# RS232.net
KiCad netlist of a schematic drawn in Altium Designer
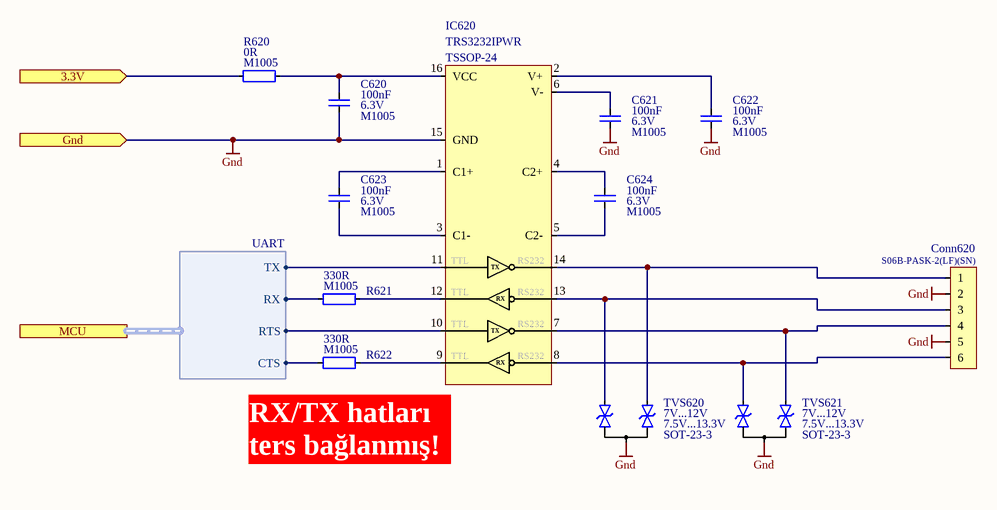
[diagram p0: RS232.SchDoc]

(export (version "E")
  (design (tool "Eeschema 10.0.6"))
  (components
    (comp (ref "C620")
      (value "100nF")
      (footprint "Capacitor_Ceramic_M1005_I0402")
      (description "Cap, Cer, 100nF, 6.3V, M1005")
      (fields
        (field (name "VOLTAGE") "6.3V")
        (field (name "MANUFACTURER PART NUMBER") "04026D104KAT4A")
        (field (name "MANUFACTURER") "Kyocera")
        (field (name "PACKAGE") "M1005")
      )
      (libsource (lib "Capacitor") (part "Capacitor_Ceramic"))
    )
    (comp (ref "C621")
      (value "100nF")
      (footprint "Capacitor_Ceramic_M1005_I0402")
      (description "Cap, Cer, 100nF, 6.3V, M1005")
      (fields
        (field (name "VOLTAGE") "6.3V")
        (field (name "MANUFACTURER PART NUMBER") "04026D104KAT4A")
        (field (name "MANUFACTURER") "Kyocera")
        (field (name "PACKAGE") "M1005")
      )
      (libsource (lib "Capacitor") (part "Capacitor_Ceramic"))
    )
    (comp (ref "C622")
      (value "100nF")
      (footprint "Capacitor_Ceramic_M1005_I0402")
      (description "Cap, Cer, 100nF, 6.3V, M1005")
      (fields
        (field (name "VOLTAGE") "6.3V")
        (field (name "MANUFACTURER PART NUMBER") "04026D104KAT4A")
        (field (name "MANUFACTURER") "Kyocera")
        (field (name "PACKAGE") "M1005")
      )
      (libsource (lib "Capacitor") (part "Capacitor_Ceramic"))
    )
    (comp (ref "C623")
      (value "100nF")
      (footprint "Capacitor_Ceramic_M1005_I0402")
      (description "Cap, Cer, 100nF, 6.3V, M1005")
      (fields
        (field (name "VOLTAGE") "6.3V")
        (field (name "MANUFACTURER PART NUMBER") "04026D104KAT4A")
        (field (name "MANUFACTURER") "Kyocera")
        (field (name "PACKAGE") "M1005")
      )
      (libsource (lib "Capacitor") (part "Capacitor_Ceramic"))
    )
    (comp (ref "C624")
      (value "100nF")
      (footprint "Capacitor_Ceramic_M1005_I0402")
      (description "Cap, Cer, 100nF, 6.3V, M1005")
      (fields
        (field (name "VOLTAGE") "6.3V")
        (field (name "MANUFACTURER PART NUMBER") "04026D104KAT4A")
        (field (name "MANUFACTURER") "Kyocera")
        (field (name "PACKAGE") "M1005")
      )
      (libsource (lib "Capacitor") (part "Capacitor_Ceramic"))
    )
    (comp (ref "Conn620")
      (value "Connector - 6P")
      (footprint "Connector, S06B-PASK-2")
      (description "Conn, JST, 6P, TH, PA, Side Entry")
      (fields
        (field (name "MANUFACTURER") "JST")
        (field (name "MANUFACTURER PART NUMBER") "S06B-PASK-2(LF)(SN)")
      )
      (libsource (lib "Connector - JST") (part "Connector - 6P"))
    )
    (comp (ref "IC620")
      (value "RS232 - Texas, TRS3232IPWR")
      (footprint "TSSOP-16")
      (description "IC, Interface, RS232, TSSOP-24")
      (fields
        (field (name "MANUFACTURER") "Texas")
        (field (name "MANUFACTURER PART NUMBER") "TRS3232IPWR")
        (field (name "PACKAGE") "TSSOP-24")
      )
      (libsource (lib "IC - Interface") (part "RS232 - Texas, TRS3232IPWR"))
    )
    (comp (ref "R620")
      (value "0R")
      (footprint "Resistor_Smd_M1005_I0402")
      (description "Res, 0R, M1005")
      (fields
        (field (name "MANUFACTURER") "Yageo")
        (field (name "MANUFACTURER PART NUMBER") "RC0402FR-070RL")
        (field (name "PACKAGE") "M1005")
      )
      (libsource (lib "Resistor") (part "Resistor"))
    )
    (comp (ref "R621")
      (value "330R")
      (footprint "Resistor_Smd_M1005_I0402")
      (description "Res, 330R, 1%, M1005")
      (fields
        (field (name "TOLERANCE") "1%")
        (field (name "MANUFACTURER") "Yageo")
        (field (name "PACKAGE") "M1005")
      )
      (libsource (lib "Resistor") (part "Resistor"))
    )
    (comp (ref "R622")
      (value "330R")
      (footprint "Resistor_Smd_M1005_I0402")
      (description "Res, 330R, 1%, M1005")
      (fields
        (field (name "TOLERANCE") "1%")
        (field (name "MANUFACTURER") "Yageo")
        (field (name "PACKAGE") "M1005")
      )
      (libsource (lib "Resistor") (part "Resistor"))
    )
    (comp (ref "TVS620")
      (value "Diode_Tvs_2P_Bidirectional")
      (footprint "Diode_SOT-23-3_2P_Bidirectional_Type_1")
      (description "TVS, 2P, Bidirectional, 7V/12V, SOT-23-3")
      (fields
        (field (name "MANUFACTURER PART NUMBER") "CDSOT23-SM712")
        (field (name "MANUFACTURER") "Bourns")
        (field (name "VOLTAGE, BREAK DOWN") "7.5V...13.3V")
        (field (name "VOLTAGE, STAND OFF") "7V...12V")
        (field (name "PACKAGE") "SOT-23-3")
      )
      (libsource (lib "Diode") (part "Diode_Tvs_2P_Bidirectional"))
    )
    (comp (ref "TVS621")
      (value "Diode_Tvs_2P_Bidirectional")
      (footprint "Diode_SOT-23-3_2P_Bidirectional_Type_1")
      (description "TVS, 2P, Bidirectional, 7V/12V, SOT-23-3")
      (fields
        (field (name "MANUFACTURER PART NUMBER") "CDSOT23-SM712")
        (field (name "MANUFACTURER") "Bourns")
        (field (name "VOLTAGE, BREAK DOWN") "7.5V...13.3V")
        (field (name "VOLTAGE, STAND OFF") "7V...12V")
        (field (name "PACKAGE") "SOT-23-3")
      )
      (libsource (lib "Diode") (part "Diode_Tvs_2P_Bidirectional"))
    )
  )
  (nets
    (net (code "2") (name "/3.3V") (class "Default")
      (node (ref "R620") (pin "1") (pinfunction "1_1") (pintype "passive"))
    )
    (net (code "3") (name "/CTS") (class "Default")
      (node (ref "R622") (pin "1") (pinfunction "1_1") (pintype "passive"))
    )
    (net (code "4") (name "/RTS") (class "Default")
      (node (ref "IC620") (pin "10") (pinfunction "DIN2_10") (pintype "passive"))
    )
    (net (code "5") (name "/RX") (class "Default")
      (node (ref "R621") (pin "1") (pinfunction "1_1") (pintype "passive"))
    )
    (net (code "6") (name "/TX") (class "Default")
      (node (ref "IC620") (pin "11") (pinfunction "DIN1_11") (pintype "passive"))
    )
    (net (code "8") (name "Gnd") (class "Default")
      (node (ref "C620") (pin "2") (pinfunction "2_2") (pintype "passive"))
      (node (ref "C621") (pin "2") (pinfunction "2_2") (pintype "passive"))
      (node (ref "C622") (pin "2") (pinfunction "2_2") (pintype "passive"))
      (node (ref "Conn620") (pin "2") (pinfunction "2_2") (pintype "passive"))
      (node (ref "Conn620") (pin "5") (pinfunction "5_5") (pintype "passive"))
      (node (ref "IC620") (pin "15") (pinfunction "GND_15") (pintype "passive"))
      (node (ref "TVS620") (pin "Common") (pinfunction "Common_Common") (pintype "passive"))
      (node (ref "TVS621") (pin "Common") (pinfunction "Common_Common") (pintype "passive"))
    )
    (net (code "9") (name "Net-(IC620-C1+)") (class "Default")
      (node (ref "C623") (pin "1") (pinfunction "1_1") (pintype "passive"))
      (node (ref "IC620") (pin "1") (pinfunction "C1+_1") (pintype "passive"))
    )
    (net (code "10") (name "Net-(IC620-C1-)") (class "Default")
      (node (ref "C623") (pin "2") (pinfunction "2_2") (pintype "passive"))
      (node (ref "IC620") (pin "3") (pinfunction "C1-_3") (pintype "passive"))
    )
    (net (code "11") (name "Net-(IC620-C2+)") (class "Default")
      (node (ref "C624") (pin "1") (pinfunction "1_1") (pintype "passive"))
      (node (ref "IC620") (pin "4") (pinfunction "C2+_4") (pintype "passive"))
    )
    (net (code "12") (name "Net-(IC620-C2-)") (class "Default")
      (node (ref "C624") (pin "2") (pinfunction "2_2") (pintype "passive"))
      (node (ref "IC620") (pin "5") (pinfunction "C2-_5") (pintype "passive"))
    )
    (net (code "13") (name "Net-(IC620-DOUT1)") (class "Default")
      (node (ref "Conn620") (pin "1") (pinfunction "1_1") (pintype "passive"))
      (node (ref "IC620") (pin "14") (pinfunction "DOUT1_14") (pintype "passive"))
      (node (ref "TVS620") (pin "D2") (pinfunction "D2_D2") (pintype "passive"))
    )
    (net (code "14") (name "Net-(IC620-DOUT2)") (class "Default")
      (node (ref "Conn620") (pin "4") (pinfunction "4_4") (pintype "passive"))
      (node (ref "IC620") (pin "7") (pinfunction "DOUT2_7") (pintype "passive"))
      (node (ref "TVS621") (pin "D2") (pinfunction "D2_D2") (pintype "passive"))
    )
    (net (code "15") (name "Net-(IC620-RIN1)") (class "Default")
      (node (ref "Conn620") (pin "3") (pinfunction "3_3") (pintype "passive"))
      (node (ref "IC620") (pin "13") (pinfunction "RIN1_13") (pintype "passive"))
      (node (ref "TVS620") (pin "D1") (pinfunction "D1_D1") (pintype "passive"))
    )
    (net (code "16") (name "Net-(IC620-RIN2)") (class "Default")
      (node (ref "Conn620") (pin "6") (pinfunction "6_6") (pintype "passive"))
      (node (ref "IC620") (pin "8") (pinfunction "RIN2_8") (pintype "passive"))
      (node (ref "TVS621") (pin "D1") (pinfunction "D1_D1") (pintype "passive"))
    )
    (net (code "17") (name "Net-(IC620-ROUT1)") (class "Default")
      (node (ref "IC620") (pin "12") (pinfunction "ROUT1_12") (pintype "passive"))
      (node (ref "R621") (pin "2") (pinfunction "2_2") (pintype "passive"))
    )
    (net (code "18") (name "Net-(IC620-ROUT2)") (class "Default")
      (node (ref "IC620") (pin "9") (pinfunction "ROUT2_9") (pintype "passive"))
      (node (ref "R622") (pin "2") (pinfunction "2_2") (pintype "passive"))
    )
    (net (code "19") (name "Net-(IC620-V+)") (class "Default")
      (node (ref "C622") (pin "1") (pinfunction "1_1") (pintype "passive"))
      (node (ref "IC620") (pin "2") (pinfunction "V+_2") (pintype "passive"))
    )
    (net (code "20") (name "Net-(IC620-V-)") (class "Default")
      (node (ref "C621") (pin "1") (pinfunction "1_1") (pintype "passive"))
      (node (ref "IC620") (pin "6") (pinfunction "V-_6") (pintype "passive"))
    )
    (net (code "21") (name "Net-(IC620-VCC)") (class "Default")
      (node (ref "C620") (pin "1") (pinfunction "1_1") (pintype "passive"))
      (node (ref "IC620") (pin "16") (pinfunction "VCC_16") (pintype "passive"))
      (node (ref "R620") (pin "2") (pinfunction "2_2") (pintype "passive"))
    )
  )
)
